# SCH_Micro_USB_2022-05-16.net
KiCad netlist of a schematic drawn in EasyEDA
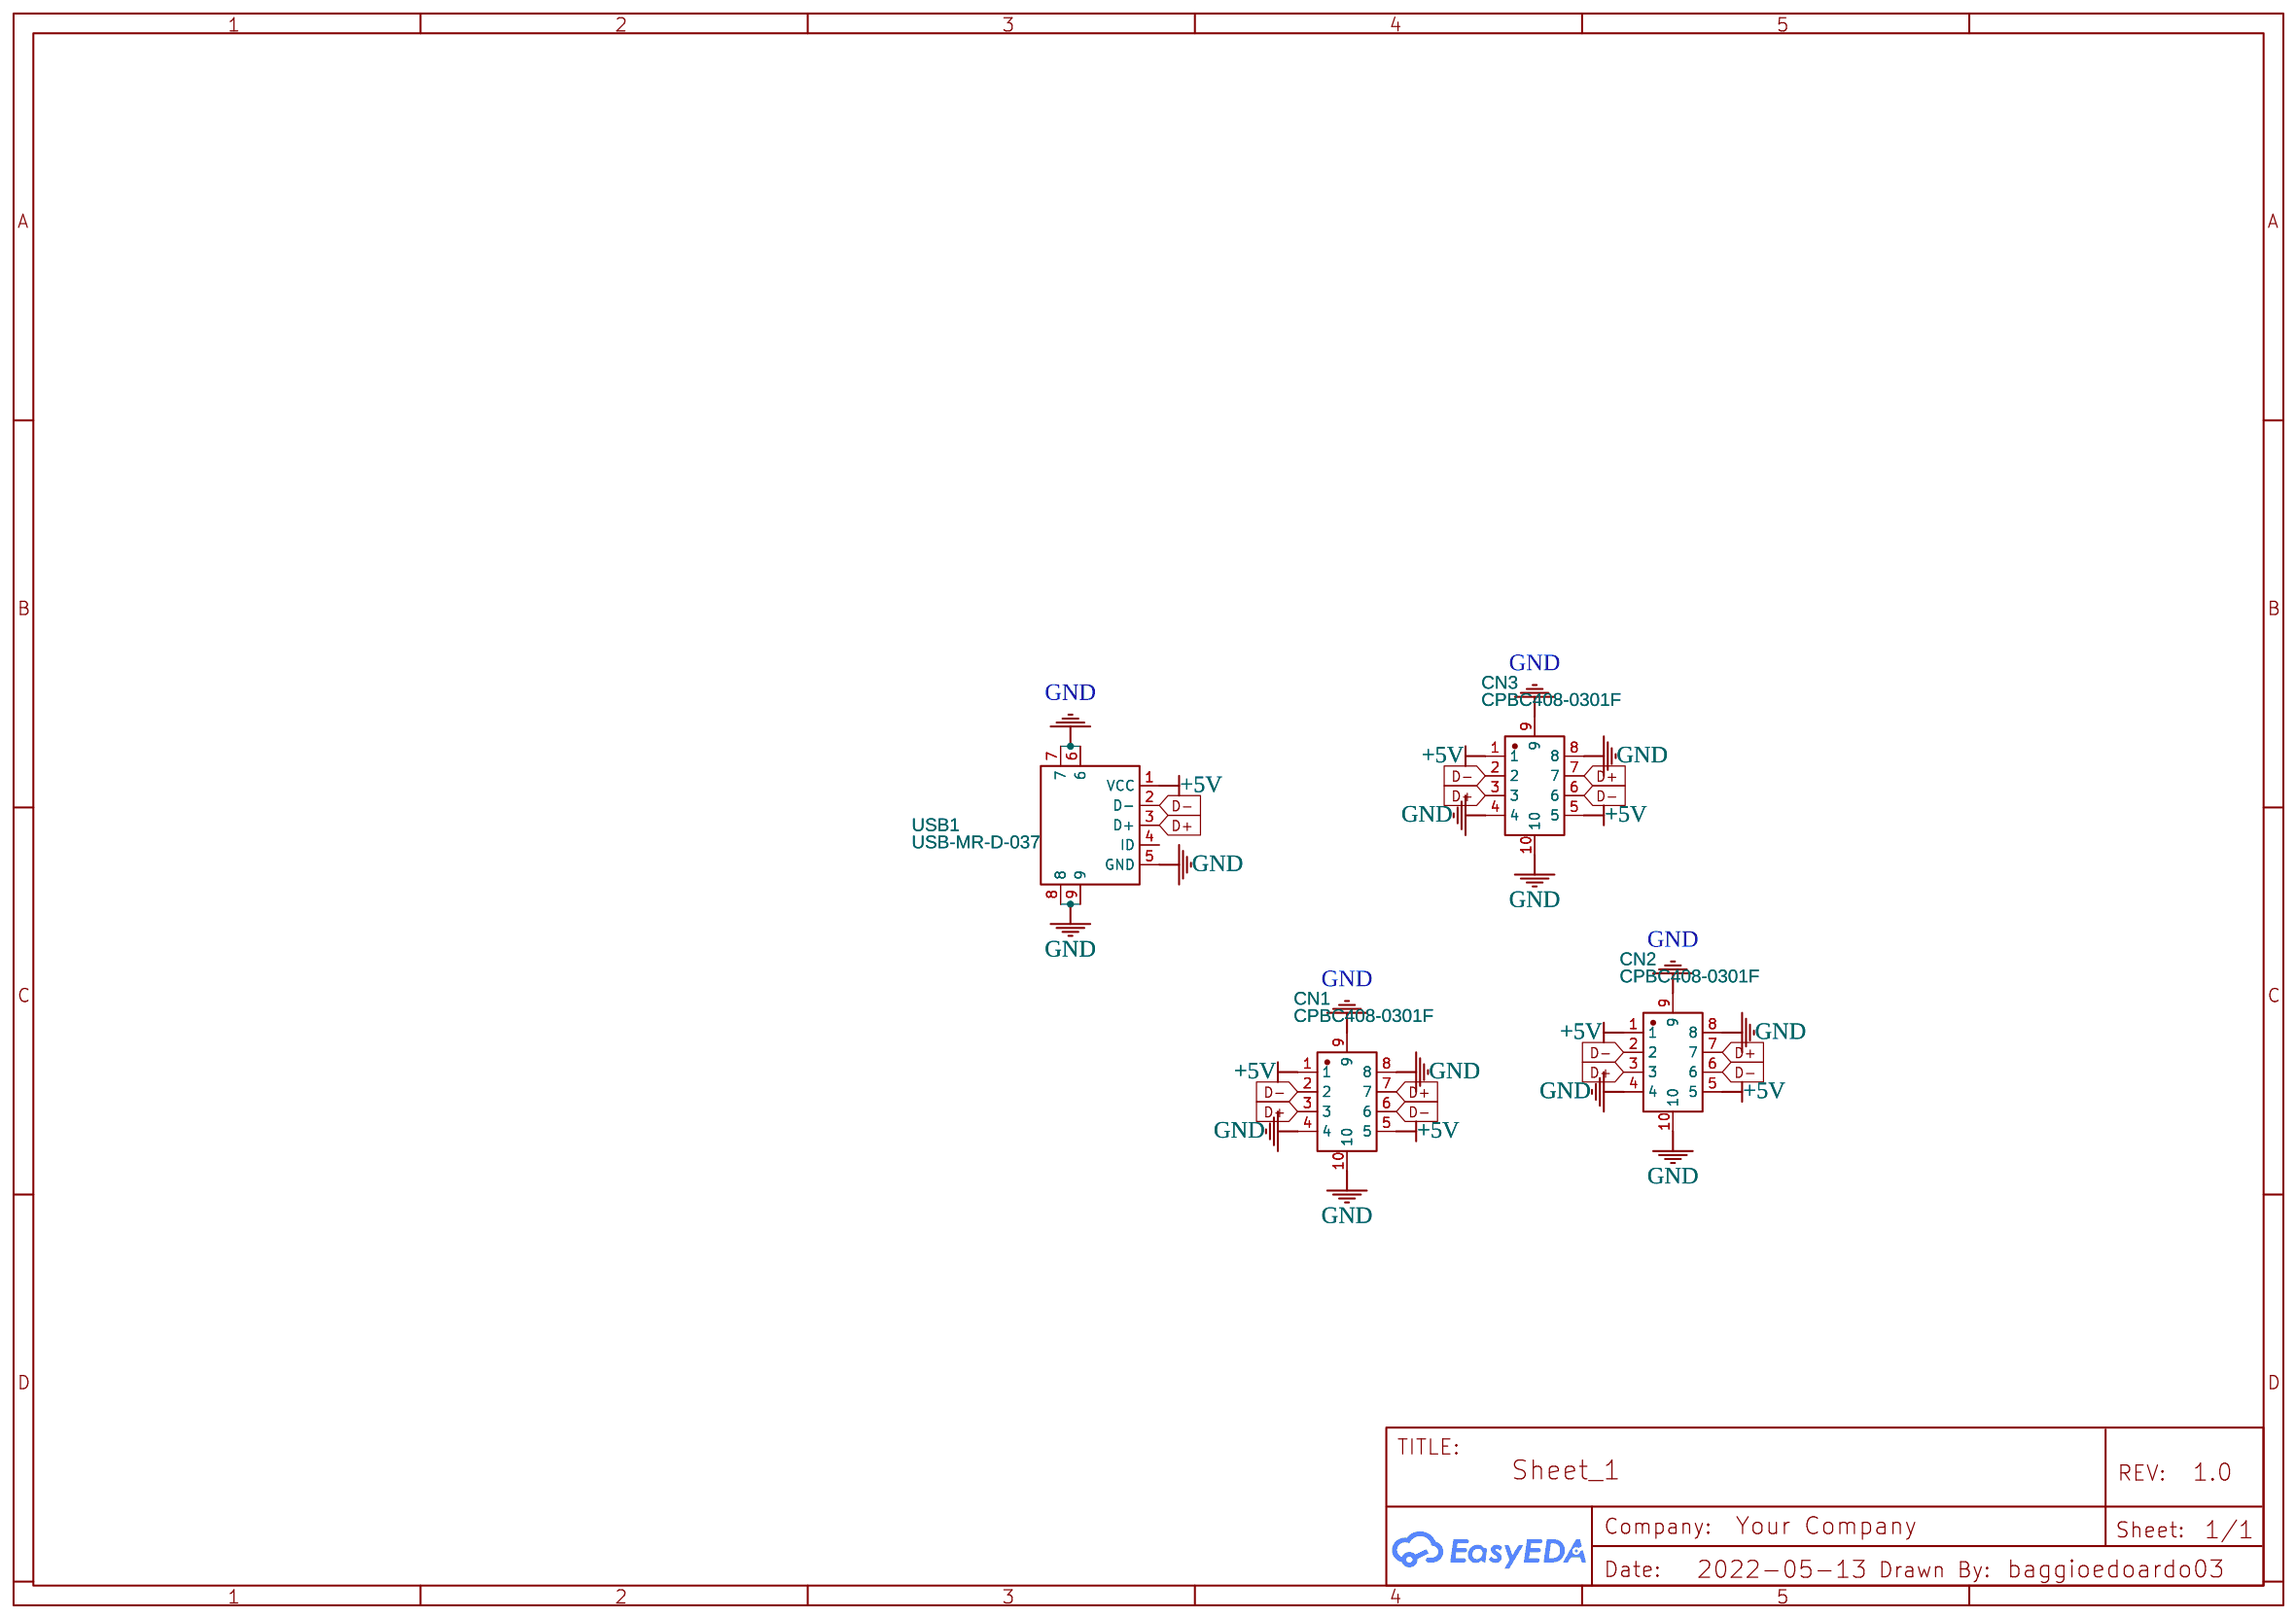
[diagram p0: schematic sheet]

(export (version "E")
  (design (tool "Eeschema 10.0.6"))
  (components
    (comp (ref "CN1")
      (value "CPBC408-0301F")
      (fields (field (name "BOM_Supplier Part") "C841002"))
      (libsource (lib "") (part "CPBC408-0301F"))
    )
    (comp (ref "CN2")
      (value "CPBC408-0301F")
      (fields (field (name "BOM_Supplier Part") "C841002"))
      (libsource (lib "") (part "CPBC408-0301F"))
    )
    (comp (ref "CN3")
      (value "CPBC408-0301F")
      (fields (field (name "BOM_Supplier Part") "C841002"))
      (libsource (lib "") (part "CPBC408-0301F"))
    )
    (comp (ref "USB1")
      (value "USB-MR-D-037")
      (fields (field (name "BOM_Supplier Part") "C2927008"))
      (libsource (lib "") (part "USB-MR-D-037"))
    )
  )
  (nets
    (net (code "1") (name "+5V") (class "Default")
      (node (ref "CN1") (pin "1") (pinfunction "1_1") (pintype "unspecified"))
      (node (ref "CN1") (pin "5") (pinfunction "5_5") (pintype "unspecified"))
      (node (ref "CN2") (pin "1") (pinfunction "1_1") (pintype "unspecified"))
      (node (ref "CN2") (pin "5") (pinfunction "5_5") (pintype "unspecified"))
      (node (ref "CN3") (pin "1") (pinfunction "1_1") (pintype "unspecified"))
      (node (ref "CN3") (pin "5") (pinfunction "5_5") (pintype "unspecified"))
      (node (ref "USB1") (pin "1") (pinfunction "VCC_1") (pintype "input"))
    )
    (net (code "2") (name "D+") (class "Default")
      (node (ref "CN1") (pin "3") (pinfunction "3_3") (pintype "unspecified"))
      (node (ref "CN1") (pin "7") (pinfunction "7_7") (pintype "unspecified"))
      (node (ref "CN2") (pin "3") (pinfunction "3_3") (pintype "unspecified"))
      (node (ref "CN2") (pin "7") (pinfunction "7_7") (pintype "unspecified"))
      (node (ref "CN3") (pin "3") (pinfunction "3_3") (pintype "unspecified"))
      (node (ref "CN3") (pin "7") (pinfunction "7_7") (pintype "unspecified"))
      (node (ref "USB1") (pin "3") (pinfunction "D+_3") (pintype "input"))
    )
    (net (code "3") (name "D-") (class "Default")
      (node (ref "CN1") (pin "2") (pinfunction "2_2") (pintype "unspecified"))
      (node (ref "CN1") (pin "6") (pinfunction "6_6") (pintype "unspecified"))
      (node (ref "CN2") (pin "2") (pinfunction "2_2") (pintype "unspecified"))
      (node (ref "CN2") (pin "6") (pinfunction "6_6") (pintype "unspecified"))
      (node (ref "CN3") (pin "2") (pinfunction "2_2") (pintype "unspecified"))
      (node (ref "CN3") (pin "6") (pinfunction "6_6") (pintype "unspecified"))
      (node (ref "USB1") (pin "2") (pinfunction "D-_2") (pintype "input"))
    )
    (net (code "4") (name "GND") (class "Default")
      (node (ref "CN1") (pin "10") (pinfunction "10_10") (pintype "unspecified"))
      (node (ref "CN1") (pin "4") (pinfunction "4_4") (pintype "unspecified"))
      (node (ref "CN1") (pin "8") (pinfunction "8_8") (pintype "unspecified"))
      (node (ref "CN1") (pin "9") (pinfunction "9_9") (pintype "unspecified"))
      (node (ref "CN2") (pin "10") (pinfunction "10_10") (pintype "unspecified"))
      (node (ref "CN2") (pin "4") (pinfunction "4_4") (pintype "unspecified"))
      (node (ref "CN2") (pin "8") (pinfunction "8_8") (pintype "unspecified"))
      (node (ref "CN2") (pin "9") (pinfunction "9_9") (pintype "unspecified"))
      (node (ref "CN3") (pin "10") (pinfunction "10_10") (pintype "unspecified"))
      (node (ref "CN3") (pin "4") (pinfunction "4_4") (pintype "unspecified"))
      (node (ref "CN3") (pin "8") (pinfunction "8_8") (pintype "unspecified"))
      (node (ref "CN3") (pin "9") (pinfunction "9_9") (pintype "unspecified"))
      (node (ref "USB1") (pin "5") (pinfunction "GND_5") (pintype "input"))
      (node (ref "USB1") (pin "6") (pinfunction "6_6") (pintype "unspecified"))
      (node (ref "USB1") (pin "7") (pinfunction "7_7") (pintype "unspecified"))
      (node (ref "USB1") (pin "8") (pinfunction "8_8") (pintype "unspecified"))
      (node (ref "USB1") (pin "9") (pinfunction "9_9") (pintype "unspecified"))
    )
    (net (code "5") (name "unconnected-(USB1-ID-Pad4)") (class "Default")
      (node (ref "USB1") (pin "4") (pinfunction "ID_4") (pintype "input"))
    )
  )
)
